# Ports.net
KiCad netlist of a schematic drawn in Altium Designer
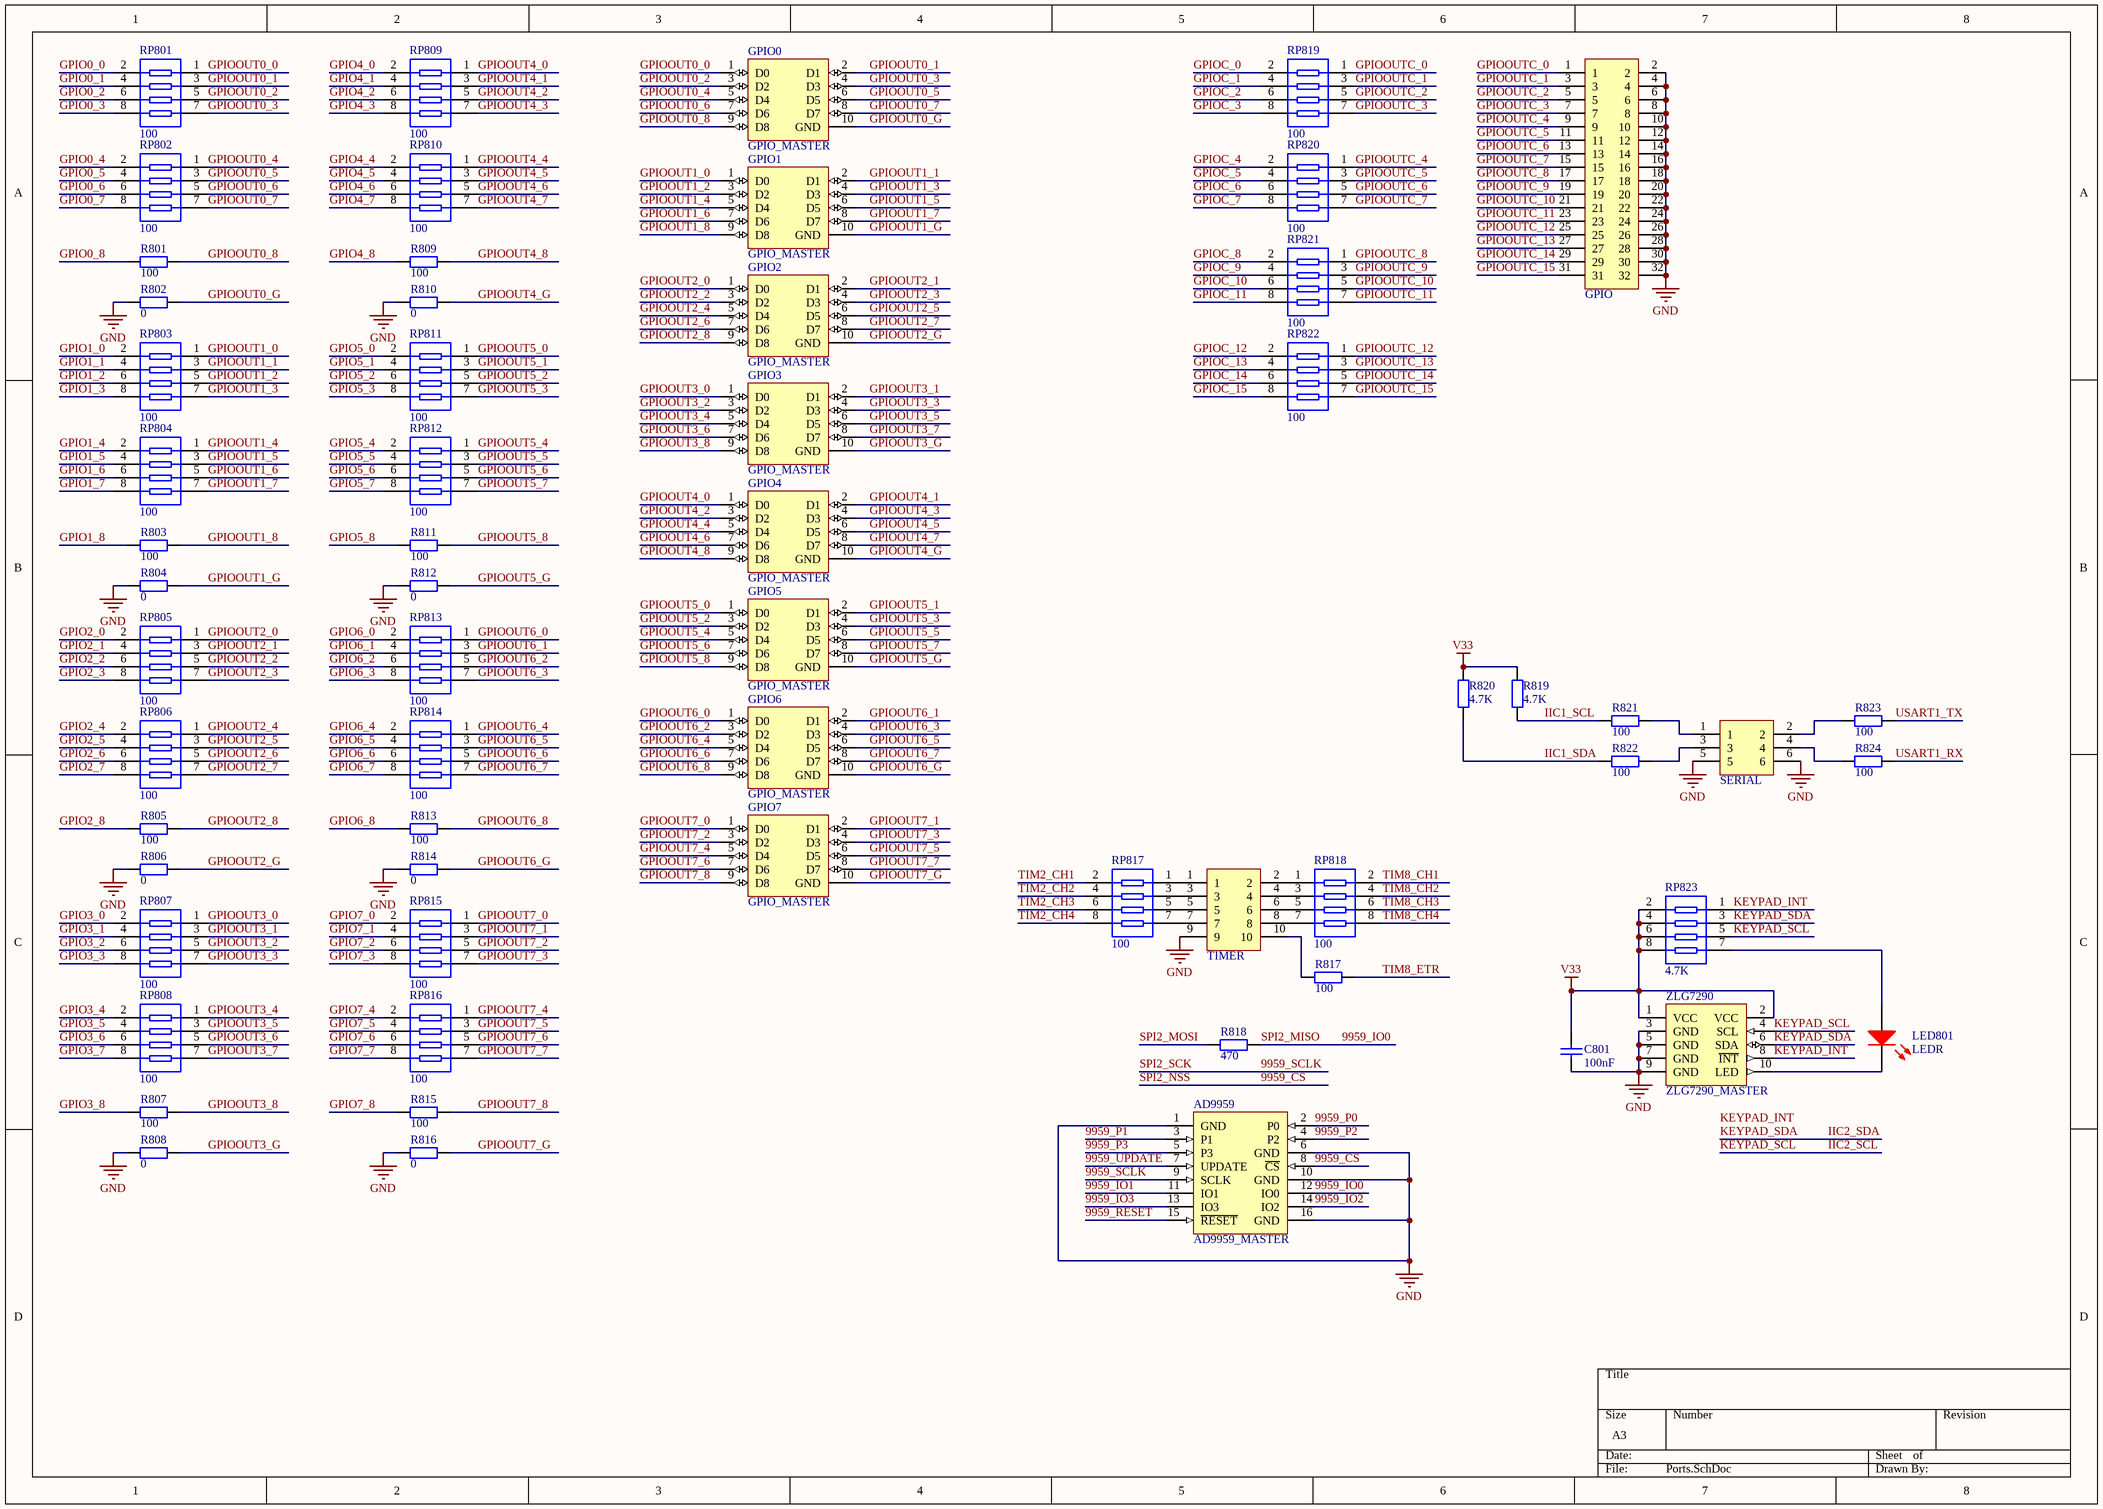
[diagram p0: Ports.SchDoc]

(export (version "E")
  (design (tool "Eeschema 10.0.6"))
  (components
    (comp (ref "AD9959")
      (value "AD9959_MASTER")
      (footprint "IDC16")
      (description "DDS module")
      (libsource (lib "Modules") (part "AD9959_MASTER"))
    )
    (comp (ref "C801")
      (value "100nF")
      (footprint "0805C")
      (description "MLCC")
      (libsource (lib "Misc") (part "MLCC"))
    )
    (comp (ref "GPIO")
      (value "Dual 16 pin port")
      (footprint "201S2X16")
      (libsource (lib "Ports2.54") (part "DPORT16"))
    )
    (comp (ref "GPIO0")
      (value "GPIO_MASTER")
      (footprint "IDC10")
      (libsource (lib "Modules") (part "GPIO_MASTER"))
    )
    (comp (ref "GPIO1")
      (value "GPIO_MASTER")
      (footprint "IDC10")
      (libsource (lib "Modules") (part "GPIO_MASTER"))
    )
    (comp (ref "GPIO2")
      (value "GPIO_MASTER")
      (footprint "IDC10")
      (libsource (lib "Modules") (part "GPIO_MASTER"))
    )
    (comp (ref "GPIO3")
      (value "GPIO_MASTER")
      (footprint "IDC10")
      (libsource (lib "Modules") (part "GPIO_MASTER"))
    )
    (comp (ref "GPIO4")
      (value "GPIO_MASTER")
      (footprint "IDC10")
      (libsource (lib "Modules") (part "GPIO_MASTER"))
    )
    (comp (ref "GPIO5")
      (value "GPIO_MASTER")
      (footprint "IDC10")
      (libsource (lib "Modules") (part "GPIO_MASTER"))
    )
    (comp (ref "GPIO6")
      (value "GPIO_MASTER")
      (footprint "IDC10")
      (libsource (lib "Modules") (part "GPIO_MASTER"))
    )
    (comp (ref "GPIO7")
      (value "GPIO_MASTER")
      (footprint "IDC10")
      (libsource (lib "Modules") (part "GPIO_MASTER"))
    )
    (comp (ref "LED801")
      (value "LEDR")
      (footprint "LED1206R")
      (description "RED LED")
      (libsource (lib "Misc") (part "LEDR"))
    )
    (comp (ref "R801")
      (value "100")
      (footprint "0603R")
      (description "Resistor")
      (libsource (lib "Misc") (part "Resistor"))
    )
    (comp (ref "R802")
      (value "0")
      (footprint "0603R")
      (description "Resistor")
      (libsource (lib "Misc") (part "Resistor"))
    )
    (comp (ref "R803")
      (value "100")
      (footprint "0603R")
      (description "Resistor")
      (libsource (lib "Misc") (part "Resistor"))
    )
    (comp (ref "R804")
      (value "0")
      (footprint "0603R")
      (description "Resistor")
      (libsource (lib "Misc") (part "Resistor"))
    )
    (comp (ref "R805")
      (value "100")
      (footprint "0603R")
      (description "Resistor")
      (libsource (lib "Misc") (part "Resistor"))
    )
    (comp (ref "R806")
      (value "0")
      (footprint "0603R")
      (description "Resistor")
      (libsource (lib "Misc") (part "Resistor"))
    )
    (comp (ref "R807")
      (value "100")
      (footprint "0603R")
      (description "Resistor")
      (libsource (lib "Misc") (part "Resistor"))
    )
    (comp (ref "R808")
      (value "0")
      (footprint "0603R")
      (description "Resistor")
      (libsource (lib "Misc") (part "Resistor"))
    )
    (comp (ref "R809")
      (value "100")
      (footprint "0603R")
      (description "Resistor")
      (libsource (lib "Misc") (part "Resistor"))
    )
    (comp (ref "R810")
      (value "0")
      (footprint "0603R")
      (description "Resistor")
      (libsource (lib "Misc") (part "Resistor"))
    )
    (comp (ref "R811")
      (value "100")
      (footprint "0603R")
      (description "Resistor")
      (libsource (lib "Misc") (part "Resistor"))
    )
    (comp (ref "R812")
      (value "0")
      (footprint "0603R")
      (description "Resistor")
      (libsource (lib "Misc") (part "Resistor"))
    )
    (comp (ref "R813")
      (value "100")
      (footprint "0603R")
      (description "Resistor")
      (libsource (lib "Misc") (part "Resistor"))
    )
    (comp (ref "R814")
      (value "0")
      (footprint "0603R")
      (description "Resistor")
      (libsource (lib "Misc") (part "Resistor"))
    )
    (comp (ref "R815")
      (value "100")
      (footprint "0603R")
      (description "Resistor")
      (libsource (lib "Misc") (part "Resistor"))
    )
    (comp (ref "R816")
      (value "0")
      (footprint "0603R")
      (description "Resistor")
      (libsource (lib "Misc") (part "Resistor"))
    )
    (comp (ref "R817")
      (value "100")
      (footprint "0603R")
      (description "Resistor")
      (libsource (lib "Misc") (part "Resistor"))
    )
    (comp (ref "R818")
      (value "470")
      (footprint "0603R")
      (description "Resistor")
      (libsource (lib "Misc") (part "Resistor"))
    )
    (comp (ref "R819")
      (value "4.7K")
      (footprint "0603R")
      (description "Resistor")
      (libsource (lib "") (part "Resistor_1"))
    )
    (comp (ref "R820")
      (value "4.7K")
      (footprint "0603R")
      (description "Resistor")
      (libsource (lib "") (part "Resistor_1"))
    )
    (comp (ref "R821")
      (value "100")
      (footprint "0603R")
      (description "Resistor")
      (libsource (lib "Misc") (part "Resistor"))
    )
    (comp (ref "R822")
      (value "100")
      (footprint "0603R")
      (description "Resistor")
      (libsource (lib "Misc") (part "Resistor"))
    )
    (comp (ref "R823")
      (value "100")
      (footprint "0603R")
      (description "Resistor")
      (libsource (lib "Misc") (part "Resistor"))
    )
    (comp (ref "R824")
      (value "100")
      (footprint "0603R")
      (description "Resistor")
      (libsource (lib "Misc") (part "Resistor"))
    )
    (comp (ref "RP801")
      (value "100")
      (footprint "8P4R_0603")
      (description "Isolated Resistor Network")
      (fields (field (name "Comment") "Res Pack"))
      (libsource (lib "Misc") (part "Res Pack"))
    )
    (comp (ref "RP802")
      (value "100")
      (footprint "8P4R_0603")
      (description "Isolated Resistor Network")
      (fields (field (name "Comment") "Res Pack"))
      (libsource (lib "Misc") (part "Res Pack"))
    )
    (comp (ref "RP803")
      (value "100")
      (footprint "8P4R_0603")
      (description "Isolated Resistor Network")
      (fields (field (name "Comment") "Res Pack"))
      (libsource (lib "Misc") (part "Res Pack"))
    )
    (comp (ref "RP804")
      (value "100")
      (footprint "8P4R_0603")
      (description "Isolated Resistor Network")
      (fields (field (name "Comment") "Res Pack"))
      (libsource (lib "Misc") (part "Res Pack"))
    )
    (comp (ref "RP805")
      (value "100")
      (footprint "8P4R_0603")
      (description "Isolated Resistor Network")
      (fields (field (name "Comment") "Res Pack"))
      (libsource (lib "Misc") (part "Res Pack"))
    )
    (comp (ref "RP806")
      (value "100")
      (footprint "8P4R_0603")
      (description "Isolated Resistor Network")
      (fields (field (name "Comment") "Res Pack"))
      (libsource (lib "Misc") (part "Res Pack"))
    )
    (comp (ref "RP807")
      (value "100")
      (footprint "8P4R_0603")
      (description "Isolated Resistor Network")
      (fields (field (name "Comment") "Res Pack"))
      (libsource (lib "Misc") (part "Res Pack"))
    )
    (comp (ref "RP808")
      (value "100")
      (footprint "8P4R_0603")
      (description "Isolated Resistor Network")
      (fields (field (name "Comment") "Res Pack"))
      (libsource (lib "Misc") (part "Res Pack"))
    )
    (comp (ref "RP809")
      (value "100")
      (footprint "8P4R_0603")
      (description "Isolated Resistor Network")
      (fields (field (name "Comment") "Res Pack"))
      (libsource (lib "Misc") (part "Res Pack"))
    )
    (comp (ref "RP810")
      (value "100")
      (footprint "8P4R_0603")
      (description "Isolated Resistor Network")
      (fields (field (name "Comment") "Res Pack"))
      (libsource (lib "Misc") (part "Res Pack"))
    )
    (comp (ref "RP811")
      (value "100")
      (footprint "8P4R_0603")
      (description "Isolated Resistor Network")
      (fields (field (name "Comment") "Res Pack"))
      (libsource (lib "Misc") (part "Res Pack"))
    )
    (comp (ref "RP812")
      (value "100")
      (footprint "8P4R_0603")
      (description "Isolated Resistor Network")
      (fields (field (name "Comment") "Res Pack"))
      (libsource (lib "Misc") (part "Res Pack"))
    )
    (comp (ref "RP813")
      (value "100")
      (footprint "8P4R_0603")
      (description "Isolated Resistor Network")
      (fields (field (name "Comment") "Res Pack"))
      (libsource (lib "Misc") (part "Res Pack"))
    )
    (comp (ref "RP814")
      (value "100")
      (footprint "8P4R_0603")
      (description "Isolated Resistor Network")
      (fields (field (name "Comment") "Res Pack"))
      (libsource (lib "Misc") (part "Res Pack"))
    )
    (comp (ref "RP815")
      (value "100")
      (footprint "8P4R_0603")
      (description "Isolated Resistor Network")
      (fields (field (name "Comment") "Res Pack"))
      (libsource (lib "Misc") (part "Res Pack"))
    )
    (comp (ref "RP816")
      (value "100")
      (footprint "8P4R_0603")
      (description "Isolated Resistor Network")
      (fields (field (name "Comment") "Res Pack"))
      (libsource (lib "Misc") (part "Res Pack"))
    )
    (comp (ref "RP817")
      (value "100")
      (footprint "8P4R_0603")
      (description "Isolated Resistor Network")
      (fields (field (name "Comment") "Res Pack"))
      (libsource (lib "Misc") (part "Res Pack"))
    )
    (comp (ref "RP818")
      (value "100")
      (footprint "8P4R_0603")
      (description "Isolated Resistor Network")
      (fields (field (name "Comment") "Res Pack"))
      (libsource (lib "Misc") (part "Res Pack"))
    )
    (comp (ref "RP819")
      (value "100")
      (footprint "8P4R_0603")
      (description "Isolated Resistor Network")
      (fields (field (name "Comment") "Res Pack"))
      (libsource (lib "Misc") (part "Res Pack"))
    )
    (comp (ref "RP820")
      (value "100")
      (footprint "8P4R_0603")
      (description "Isolated Resistor Network")
      (fields (field (name "Comment") "Res Pack"))
      (libsource (lib "Misc") (part "Res Pack"))
    )
    (comp (ref "RP821")
      (value "100")
      (footprint "8P4R_0603")
      (description "Isolated Resistor Network")
      (fields (field (name "Comment") "Res Pack"))
      (libsource (lib "Misc") (part "Res Pack"))
    )
    (comp (ref "RP822")
      (value "100")
      (footprint "8P4R_0603")
      (description "Isolated Resistor Network")
      (fields (field (name "Comment") "Res Pack"))
      (libsource (lib "Misc") (part "Res Pack"))
    )
    (comp (ref "RP823")
      (value "4.7K")
      (footprint "8P4R_0603")
      (description "Isolated Resistor Network")
      (fields (field (name "Comment") "Res Pack"))
      (libsource (lib "Misc") (part "Res Pack"))
    )
    (comp (ref "SERIAL")
      (value "Dual 3 pin port")
      (footprint "201S2X3")
      (libsource (lib "Ports2.54") (part "DPORT3"))
    )
    (comp (ref "TIMER") (value "IDC10") (footprint "IDC10") (libsource (lib "Ports2.54") (part "IDC10")))
    (comp (ref "ZLG7290")
      (value "ZLG7290_MASTER")
      (footprint "IDC10")
      (description "KEY module")
      (libsource (lib "Modules") (part "ZLG7290_MASTER"))
    )
  )
  (nets
    (net (code "1") (name "/9959_CS") (class "Default")
      (node (ref "AD9959") (pin "8") (pinfunction "~{CS}_8") (pintype "input"))
    )
    (net (code "2") (name "/9959_IO0") (class "Default")
      (node (ref "AD9959") (pin "12") (pinfunction "IO0_12") (pintype "passive"))
      (node (ref "R818") (pin "2") (pinfunction "2_2") (pintype "passive"))
    )
    (net (code "3") (name "/9959_IO1") (class "Default")
      (node (ref "AD9959") (pin "11") (pinfunction "IO1_11") (pintype "passive"))
    )
    (net (code "4") (name "/9959_IO2") (class "Default")
      (node (ref "AD9959") (pin "14") (pinfunction "IO2_14") (pintype "passive"))
    )
    (net (code "5") (name "/9959_IO3") (class "Default")
      (node (ref "AD9959") (pin "13") (pinfunction "IO3_13") (pintype "passive"))
    )
    (net (code "6") (name "/9959_P0") (class "Default")
      (node (ref "AD9959") (pin "2") (pinfunction "P0_2") (pintype "input"))
    )
    (net (code "7") (name "/9959_P1") (class "Default")
      (node (ref "AD9959") (pin "3") (pinfunction "P1_3") (pintype "input"))
    )
    (net (code "8") (name "/9959_P2") (class "Default")
      (node (ref "AD9959") (pin "4") (pinfunction "P2_4") (pintype "input"))
    )
    (net (code "9") (name "/9959_P3") (class "Default")
      (node (ref "AD9959") (pin "5") (pinfunction "P3_5") (pintype "input"))
    )
    (net (code "10") (name "/9959_RESET") (class "Default")
      (node (ref "AD9959") (pin "15") (pinfunction "~{RESET}_15") (pintype "input"))
    )
    (net (code "11") (name "/9959_SCLK") (class "Default")
      (node (ref "AD9959") (pin "9") (pinfunction "SCLK_9") (pintype "input"))
    )
    (net (code "12") (name "/9959_UPDATE") (class "Default")
      (node (ref "AD9959") (pin "7") (pinfunction "UPDATE_7") (pintype "input"))
    )
    (net (code "13") (name "/GPIO0_0") (class "Default")
      (node (ref "RP801") (pin "2") (pinfunction "2_2") (pintype "passive"))
    )
    (net (code "14") (name "/GPIO0_1") (class "Default")
      (node (ref "RP801") (pin "4") (pinfunction "4_4") (pintype "passive"))
    )
    (net (code "15") (name "/GPIO0_2") (class "Default")
      (node (ref "RP801") (pin "6") (pinfunction "6_6") (pintype "passive"))
    )
    (net (code "16") (name "/GPIO0_3") (class "Default")
      (node (ref "RP801") (pin "8") (pinfunction "8_8") (pintype "passive"))
    )
    (net (code "17") (name "/GPIO0_4") (class "Default")
      (node (ref "RP802") (pin "2") (pinfunction "2_2") (pintype "passive"))
    )
    (net (code "18") (name "/GPIO0_5") (class "Default")
      (node (ref "RP802") (pin "4") (pinfunction "4_4") (pintype "passive"))
    )
    (net (code "19") (name "/GPIO0_6") (class "Default")
      (node (ref "RP802") (pin "6") (pinfunction "6_6") (pintype "passive"))
    )
    (net (code "20") (name "/GPIO0_7") (class "Default")
      (node (ref "RP802") (pin "8") (pinfunction "8_8") (pintype "passive"))
    )
    (net (code "21") (name "/GPIO0_8") (class "Default")
      (node (ref "R801") (pin "1") (pinfunction "1_1") (pintype "passive"))
    )
    (net (code "22") (name "/GPIO1_0") (class "Default")
      (node (ref "RP803") (pin "2") (pinfunction "2_2") (pintype "passive"))
    )
    (net (code "23") (name "/GPIO1_1") (class "Default")
      (node (ref "RP803") (pin "4") (pinfunction "4_4") (pintype "passive"))
    )
    (net (code "24") (name "/GPIO1_2") (class "Default")
      (node (ref "RP803") (pin "6") (pinfunction "6_6") (pintype "passive"))
    )
    (net (code "25") (name "/GPIO1_3") (class "Default")
      (node (ref "RP803") (pin "8") (pinfunction "8_8") (pintype "passive"))
    )
    (net (code "26") (name "/GPIO1_4") (class "Default")
      (node (ref "RP804") (pin "2") (pinfunction "2_2") (pintype "passive"))
    )
    (net (code "27") (name "/GPIO1_5") (class "Default")
      (node (ref "RP804") (pin "4") (pinfunction "4_4") (pintype "passive"))
    )
    (net (code "28") (name "/GPIO1_6") (class "Default")
      (node (ref "RP804") (pin "6") (pinfunction "6_6") (pintype "passive"))
    )
    (net (code "29") (name "/GPIO1_7") (class "Default")
      (node (ref "RP804") (pin "8") (pinfunction "8_8") (pintype "passive"))
    )
    (net (code "30") (name "/GPIO1_8") (class "Default")
      (node (ref "R803") (pin "1") (pinfunction "1_1") (pintype "passive"))
    )
    (net (code "31") (name "/GPIO2_0") (class "Default")
      (node (ref "RP805") (pin "2") (pinfunction "2_2") (pintype "passive"))
    )
    (net (code "32") (name "/GPIO2_1") (class "Default")
      (node (ref "RP805") (pin "4") (pinfunction "4_4") (pintype "passive"))
    )
    (net (code "33") (name "/GPIO2_2") (class "Default")
      (node (ref "RP805") (pin "6") (pinfunction "6_6") (pintype "passive"))
    )
    (net (code "34") (name "/GPIO2_3") (class "Default")
      (node (ref "RP805") (pin "8") (pinfunction "8_8") (pintype "passive"))
    )
    (net (code "35") (name "/GPIO2_4") (class "Default")
      (node (ref "RP806") (pin "2") (pinfunction "2_2") (pintype "passive"))
    )
    (net (code "36") (name "/GPIO2_5") (class "Default")
      (node (ref "RP806") (pin "4") (pinfunction "4_4") (pintype "passive"))
    )
    (net (code "37") (name "/GPIO2_6") (class "Default")
      (node (ref "RP806") (pin "6") (pinfunction "6_6") (pintype "passive"))
    )
    (net (code "38") (name "/GPIO2_7") (class "Default")
      (node (ref "RP806") (pin "8") (pinfunction "8_8") (pintype "passive"))
    )
    (net (code "39") (name "/GPIO2_8") (class "Default")
      (node (ref "R805") (pin "1") (pinfunction "1_1") (pintype "passive"))
    )
    (net (code "40") (name "/GPIO3_0") (class "Default")
      (node (ref "RP807") (pin "2") (pinfunction "2_2") (pintype "passive"))
    )
    (net (code "41") (name "/GPIO3_1") (class "Default")
      (node (ref "RP807") (pin "4") (pinfunction "4_4") (pintype "passive"))
    )
    (net (code "42") (name "/GPIO3_2") (class "Default")
      (node (ref "RP807") (pin "6") (pinfunction "6_6") (pintype "passive"))
    )
    (net (code "43") (name "/GPIO3_3") (class "Default")
      (node (ref "RP807") (pin "8") (pinfunction "8_8") (pintype "passive"))
    )
    (net (code "44") (name "/GPIO3_4") (class "Default")
      (node (ref "RP808") (pin "2") (pinfunction "2_2") (pintype "passive"))
    )
    (net (code "45") (name "/GPIO3_5") (class "Default")
      (node (ref "RP808") (pin "4") (pinfunction "4_4") (pintype "passive"))
    )
    (net (code "46") (name "/GPIO3_6") (class "Default")
      (node (ref "RP808") (pin "6") (pinfunction "6_6") (pintype "passive"))
    )
    (net (code "47") (name "/GPIO3_7") (class "Default")
      (node (ref "RP808") (pin "8") (pinfunction "8_8") (pintype "passive"))
    )
    (net (code "48") (name "/GPIO3_8") (class "Default")
      (node (ref "R807") (pin "1") (pinfunction "1_1") (pintype "passive"))
    )
    (net (code "49") (name "/GPIO4_0") (class "Default")
      (node (ref "RP809") (pin "2") (pinfunction "2_2") (pintype "passive"))
    )
    (net (code "50") (name "/GPIO4_1") (class "Default")
      (node (ref "RP809") (pin "4") (pinfunction "4_4") (pintype "passive"))
    )
    (net (code "51") (name "/GPIO4_2") (class "Default")
      (node (ref "RP809") (pin "6") (pinfunction "6_6") (pintype "passive"))
    )
    (net (code "52") (name "/GPIO4_3") (class "Default")
      (node (ref "RP809") (pin "8") (pinfunction "8_8") (pintype "passive"))
    )
    (net (code "53") (name "/GPIO4_4") (class "Default")
      (node (ref "RP810") (pin "2") (pinfunction "2_2") (pintype "passive"))
    )
    (net (code "54") (name "/GPIO4_5") (class "Default")
      (node (ref "RP810") (pin "4") (pinfunction "4_4") (pintype "passive"))
    )
    (net (code "55") (name "/GPIO4_6") (class "Default")
      (node (ref "RP810") (pin "6") (pinfunction "6_6") (pintype "passive"))
    )
    (net (code "56") (name "/GPIO4_7") (class "Default")
      (node (ref "RP810") (pin "8") (pinfunction "8_8") (pintype "passive"))
    )
    (net (code "57") (name "/GPIO4_8") (class "Default")
      (node (ref "R809") (pin "1") (pinfunction "1_1") (pintype "passive"))
    )
    (net (code "58") (name "/GPIO5_0") (class "Default")
      (node (ref "RP811") (pin "2") (pinfunction "2_2") (pintype "passive"))
    )
    (net (code "59") (name "/GPIO5_1") (class "Default")
      (node (ref "RP811") (pin "4") (pinfunction "4_4") (pintype "passive"))
    )
    (net (code "60") (name "/GPIO5_2") (class "Default")
      (node (ref "RP811") (pin "6") (pinfunction "6_6") (pintype "passive"))
    )
    (net (code "61") (name "/GPIO5_3") (class "Default")
      (node (ref "RP811") (pin "8") (pinfunction "8_8") (pintype "passive"))
    )
    (net (code "62") (name "/GPIO5_4") (class "Default")
      (node (ref "RP812") (pin "2") (pinfunction "2_2") (pintype "passive"))
    )
    (net (code "63") (name "/GPIO5_5") (class "Default")
      (node (ref "RP812") (pin "4") (pinfunction "4_4") (pintype "passive"))
    )
    (net (code "64") (name "/GPIO5_6") (class "Default")
      (node (ref "RP812") (pin "6") (pinfunction "6_6") (pintype "passive"))
    )
    (net (code "65") (name "/GPIO5_7") (class "Default")
      (node (ref "RP812") (pin "8") (pinfunction "8_8") (pintype "passive"))
    )
    (net (code "66") (name "/GPIO5_8") (class "Default")
      (node (ref "R811") (pin "1") (pinfunction "1_1") (pintype "passive"))
    )
    (net (code "67") (name "/GPIO6_0") (class "Default")
      (node (ref "RP813") (pin "2") (pinfunction "2_2") (pintype "passive"))
    )
    (net (code "68") (name "/GPIO6_1") (class "Default")
      (node (ref "RP813") (pin "4") (pinfunction "4_4") (pintype "passive"))
    )
    (net (code "69") (name "/GPIO6_2") (class "Default")
      (node (ref "RP813") (pin "6") (pinfunction "6_6") (pintype "passive"))
    )
    (net (code "70") (name "/GPIO6_3") (class "Default")
      (node (ref "RP813") (pin "8") (pinfunction "8_8") (pintype "passive"))
    )
    (net (code "71") (name "/GPIO6_4") (class "Default")
      (node (ref "RP814") (pin "2") (pinfunction "2_2") (pintype "passive"))
    )
    (net (code "72") (name "/GPIO6_5") (class "Default")
      (node (ref "RP814") (pin "4") (pinfunction "4_4") (pintype "passive"))
    )
    (net (code "73") (name "/GPIO6_6") (class "Default")
      (node (ref "RP814") (pin "6") (pinfunction "6_6") (pintype "passive"))
    )
    (net (code "74") (name "/GPIO6_7") (class "Default")
      (node (ref "RP814") (pin "8") (pinfunction "8_8") (pintype "passive"))
    )
    (net (code "75") (name "/GPIO6_8") (class "Default")
      (node (ref "R813") (pin "1") (pinfunction "1_1") (pintype "passive"))
    )
    (net (code "76") (name "/GPIO7_0") (class "Default")
      (node (ref "RP815") (pin "2") (pinfunction "2_2") (pintype "passive"))
    )
    (net (code "77") (name "/GPIO7_1") (class "Default")
      (node (ref "RP815") (pin "4") (pinfunction "4_4") (pintype "passive"))
    )
    (net (code "78") (name "/GPIO7_2") (class "Default")
      (node (ref "RP815") (pin "6") (pinfunction "6_6") (pintype "passive"))
    )
    (net (code "79") (name "/GPIO7_3") (class "Default")
      (node (ref "RP815") (pin "8") (pinfunction "8_8") (pintype "passive"))
    )
    (net (code "80") (name "/GPIO7_4") (class "Default")
      (node (ref "RP816") (pin "2") (pinfunction "2_2") (pintype "passive"))
    )
    (net (code "81") (name "/GPIO7_5") (class "Default")
      (node (ref "RP816") (pin "4") (pinfunction "4_4") (pintype "passive"))
    )
    (net (code "82") (name "/GPIO7_6") (class "Default")
      (node (ref "RP816") (pin "6") (pinfunction "6_6") (pintype "passive"))
    )
    (net (code "83") (name "/GPIO7_7") (class "Default")
      (node (ref "RP816") (pin "8") (pinfunction "8_8") (pintype "passive"))
    )
    (net (code "84") (name "/GPIO7_8") (class "Default")
      (node (ref "R815") (pin "1") (pinfunction "1_1") (pintype "passive"))
    )
    (net (code "85") (name "/GPIOC_0") (class "Default")
      (node (ref "RP819") (pin "2") (pinfunction "2_2") (pintype "passive"))
    )
    (net (code "86") (name "/GPIOC_1") (class "Default")
      (node (ref "RP819") (pin "4") (pinfunction "4_4") (pintype "passive"))
    )
    (net (code "87") (name "/GPIOC_2") (class "Default")
      (node (ref "RP819") (pin "6") (pinfunction "6_6") (pintype "passive"))
    )
    (net (code "88") (name "/GPIOC_3") (class "Default")
      (node (ref "RP819") (pin "8") (pinfunction "8_8") (pintype "passive"))
    )
    (net (code "89") (name "/GPIOC_4") (class "Default")
      (node (ref "RP820") (pin "2") (pinfunction "2_2") (pintype "passive"))
    )
    (net (code "90") (name "/GPIOC_5") (class "Default")
      (node (ref "RP820") (pin "4") (pinfunction "4_4") (pintype "passive"))
    )
    (net (code "91") (name "/GPIOC_6") (class "Default")
      (node (ref "RP820") (pin "6") (pinfunction "6_6") (pintype "passive"))
    )
    (net (code "92") (name "/GPIOC_7") (class "Default")
      (node (ref "RP820") (pin "8") (pinfunction "8_8") (pintype "passive"))
    )
    (net (code "93") (name "/GPIOC_8") (class "Default")
      (node (ref "RP821") (pin "2") (pinfunction "2_2") (pintype "passive"))
    )
    (net (code "94") (name "/GPIOC_9") (class "Default")
      (node (ref "RP821") (pin "4") (pinfunction "4_4") (pintype "passive"))
    )
    (net (code "95") (name "/GPIOC_10") (class "Default")
      (node (ref "RP821") (pin "6") (pinfunction "6_6") (pintype "passive"))
    )
    (net (code "96") (name "/GPIOC_11") (class "Default")
      (node (ref "RP821") (pin "8") (pinfunction "8_8") (pintype "passive"))
    )
    (net (code "97") (name "/GPIOC_12") (class "Default")
      (node (ref "RP822") (pin "2") (pinfunction "2_2") (pintype "passive"))
    )
    (net (code "98") (name "/GPIOC_13") (class "Default")
      (node (ref "RP822") (pin "4") (pinfunction "4_4") (pintype "passive"))
    )
    (net (code "99") (name "/GPIOC_14") (class "Default")
      (node (ref "RP822") (pin "6") (pinfunction "6_6") (pintype "passive"))
    )
    (net (code "100") (name "/GPIOC_15") (class "Default")
      (node (ref "RP822") (pin "8") (pinfunction "8_8") (pintype "passive"))
    )
    (net (code "101") (name "/GPIOOUT0_0") (class "Default")
      (node (ref "GPIO0") (pin "1") (pinfunction "D0_1") (pintype "bidirectional"))
      (node (ref "RP801") (pin "1") (pinfunction "1_1") (pintype "passive"))
    )
    (net (code "102") (name "/GPIOOUT0_1") (class "Default")
      (node (ref "GPIO0") (pin "2") (pinfunction "D1_2") (pintype "bidirectional"))
      (node (ref "RP801") (pin "3") (pinfunction "3_3") (pintype "passive"))
    )
    (net (code "103") (name "/GPIOOUT0_2") (class "Default")
      (node (ref "GPIO0") (pin "3") (pinfunction "D2_3") (pintype "bidirectional"))
      (node (ref "RP801") (pin "5") (pinfunction "5_5") (pintype "passive"))
    )
    (net (code "104") (name "/GPIOOUT0_3") (class "Default")
      (node (ref "GPIO0") (pin "4") (pinfunction "D3_4") (pintype "bidirectional"))
      (node (ref "RP801") (pin "7") (pinfunction "7_7") (pintype "passive"))
    )
    (net (code "105") (name "/GPIOOUT0_4") (class "Default")
      (node (ref "GPIO0") (pin "5") (pinfunction "D4_5") (pintype "bidirectional"))
      (node (ref "RP802") (pin "1") (pinfunction "1_1") (pintype "passive"))
    )
    (net (code "106") (name "/GPIOOUT0_5") (class "Default")
      (node (ref "GPIO0") (pin "6") (pinfunction "D5_6") (pintype "bidirectional"))
      (node (ref "RP802") (pin "3") (pinfunction "3_3") (pintype "passive"))
    )
    (net (code "107") (name "/GPIOOUT0_6") (class "Default")
      (node (ref "GPIO0") (pin "7") (pinfunction "D6_7") (pintype "bidirectional"))
      (node (ref "RP802") (pin "5") (pinfunction "5_5") (pintype "passive"))
    )
    (net (code "108") (name "/GPIOOUT0_7") (class "Default")
      (node (ref "GPIO0") (pin "8") (pinfunction "D7_8") (pintype "bidirectional"))
      (node (ref "RP802") (pin "7") (pinfunction "7_7") (pintype "passive"))
    )
    (net (code "109") (name "/GPIOOUT0_8") (class "Default")
      (node (ref "GPIO0") (pin "9") (pinfunction "D8_9") (pintype "bidirectional"))
      (node (ref "R801") (pin "2") (pinfunction "2_2") (pintype "passive"))
    )
    (net (code "110") (name "/GPIOOUT0_G") (class "Default")
      (node (ref "GPIO0") (pin "10") (pinfunction "GND_10") (pintype "power_in"))
      (node (ref "R802") (pin "2") (pinfunction "2_2") (pintype "passive"))
    )
    (net (code "111") (name "/GPIOOUT1_0") (class "Default")
      (node (ref "GPIO1") (pin "1") (pinfunction "D0_1") (pintype "bidirectional"))
      (node (ref "RP803") (pin "1") (pinfunction "1_1") (pintype "passive"))
    )
    (net (code "112") (name "/GPIOOUT1_1") (class "Default")
      (node (ref "GPIO1") (pin "2") (pinfunction "D1_2") (pintype "bidirectional"))
      (node (ref "RP803") (pin "3") (pinfunction "3_3") (pintype "passive"))
    )
    (net (code "113") (name "/GPIOOUT1_2") (class "Default")
      (node (ref "GPIO1") (pin "3") (pinfunction "D2_3") (pintype "bidirectional"))
      (node (ref "RP803") (pin "5") (pinfunction "5_5") (pintype "passive"))
    )
    (net (code "114") (name "/GPIOOUT1_3") (class "Default")
      (node (ref "GPIO1") (pin "4") (pinfunction "D3_4") (pintype "bidirectional"))
      (node (ref "RP803") (pin "7") (pinfunction "7_7") (pintype "passive"))
    )
    (net (code "115") (name "/GPIOOUT1_4") (class "Default")
      (node (ref "GPIO1") (pin "5") (pinfunction "D4_5") (pintype "bidirectional"))
      (node (ref "RP804") (pin "1") (pinfunction "1_1") (pintype "passive"))
    )
    (net (code "116") (name "/GPIOOUT1_5") (class "Default")
      (node (ref "GPIO1") (pin "6") (pinfunction "D5_6") (pintype "bidirectional"))
      (node (ref "RP804") (pin "3") (pinfunction "3_3") (pintype "passive"))
    )
    (net (code "117") (name "/GPIOOUT1_6") (class "Default")
      (node (ref "GPIO1") (pin "7") (pinfunction "D6_7") (pintype "bidirectional"))
      (node (ref "RP804") (pin "5") (pinfunction "5_5") (pintype "passive"))
    )
    (net (code "118") (name "/GPIOOUT1_7") (class "Default")
      (node (ref "GPIO1") (pin "8") (pinfunction "D7_8") (pintype "bidirectional"))
      (node (ref "RP804") (pin "7") (pinfunction "7_7") (pintype "passive"))
    )
    (net (code "119") (name "/GPIOOUT1_8") (class "Default")
      (node (ref "GPIO1") (pin "9") (pinfunction "D8_9") (pintype "bidirectional"))
      (node (ref "R803") (pin "2") (pinfunction "2_2") (pintype "passive"))
    )
    (net (code "120") (name "/GPIOOUT1_G") (class "Default")
      (node (ref "GPIO1") (pin "10") (pinfunction "GND_10") (pintype "power_in"))
      (node (ref "R804") (pin "2") (pinfunction "2_2") (pintype "passive"))
    )
    (net (code "121") (name "/GPIOOUT2_0") (class "Default")
      (node (ref "GPIO2") (pin "1") (pinfunction "D0_1") (pintype "bidirectional"))
      (node (ref "RP805") (pin "1") (pinfunction "1_1") (pintype "passive"))
    )
    (net (code "122") (name "/GPIOOUT2_1") (class "Default")
      (node (ref "GPIO2") (pin "2") (pinfunction "D1_2") (pintype "bidirectional"))
      (node (ref "RP805") (pin "3") (pinfunction "3_3") (pintype "passive"))
    )
    (net (code "123") (name "/GPIOOUT2_2") (class "Default")
      (node (ref "GPIO2") (pin "3") (pinfunction "D2_3") (pintype "bidirectional"))
      (node (ref "RP805") (pin "5") (pinfunction "5_5") (pintype "passive"))
    )
    (net (code "124") (name "/GPIOOUT2_3") (class "Default")
      (node (ref "GPIO2") (pin "4") (pinfunction "D3_4") (pintype "bidirectional"))
      (node (ref "RP805") (pin "7") (pinfunction "7_7") (pintype "passive"))
    )
    (net (code "125") (name "/GPIOOUT2_4") (class "Default")
      (node (ref "GPIO2") (pin "5") (pinfunction "D4_5") (pintype "bidirectional"))
      (node (ref "RP806") (pin "1") (pinfunction "1_1") (pintype "passive"))
    )
    (net (code "126") (name "/GPIOOUT2_5") (class "Default")
      (node (ref "GPIO2") (pin "6") (pinfunction "D5_6") (pintype "bidirectional"))
      (node (ref "RP806") (pin "3") (pinfunction "3_3") (pintype "passive"))
    )
    (net (code "127") (name "/GPIOOUT2_6") (class "Default")
      (node (ref "GPIO2") (pin "7") (pinfunction "D6_7") (pintype "bidirectional"))
      (node (ref "RP806") (pin "5") (pinfunction "5_5") (pintype "passive"))
    )
    (net (code "128") (name "/GPIOOUT2_7") (class "Default")
      (node (ref "GPIO2") (pin "8") (pinfunction "D7_8") (pintype "bidirectional"))
      (node (ref "RP806") (pin "7") (pinfunction "7_7") (pintype "passive"))
    )
    (net (code "129") (name "/GPIOOUT2_8") (class "Default")
      (node (ref "GPIO2") (pin "9") (pinfunction "D8_9") (pintype "bidirectional"))
      (node (ref "R805") (pin "2") (pinfunction "2_2") (pintype "passive"))
    )
    (net (code "130") (name "/GPIOOUT2_G") (class "Default")
      (node (ref "GPIO2") (pin "10") (pinfunction "GND_10") (pintype "power_in"))
      (node (ref "R806") (pin "2") (pinfunction "2_2") (pintype "passive"))
    )
    (net (code "131") (name "/GPIOOUT3_0") (class "Default")
      (node (ref "GPIO3") (pin "1") (pinfunction "D0_1") (pintype "bidirectional"))
      (node (ref "RP807") (pin "1") (pinfunction "1_1") (pintype "passive"))
    )
    (net (code "132") (name "/GPIOOUT3_1") (class "Default")
      (node (ref "GPIO3") (pin "2") (pinfunction "D1_2") (pintype "bidirectional"))
      (node (ref "RP807") (pin "3") (pinfunction "3_3") (pintype "passive"))
    )
    (net (code "133") (name "/GPIOOUT3_2") (class "Default")
      (node (ref "GPIO3") (pin "3") (pinfunction "D2_3") (pintype "bidirectional"))
      (node (ref "RP807") (pin "5") (pinfunction "5_5") (pintype "passive"))
    )
    (net (code "134") (name "/GPIOOUT3_3") (class "Default")
      (node (ref "GPIO3") (pin "4") (pinfunction "D3_4") (pintype "bidirectional"))
      (node (ref "RP807") (pin "7") (pinfunction "7_7") (pintype "passive"))
    )
    (net (code "135") (name "/GPIOOUT3_4") (class "Default")
      (node (ref "GPIO3") (pin "5") (pinfunction "D4_5") (pintype "bidirectional"))
      (node (ref "RP808") (pin "1") (pinfunction "1_1") (pintype "passive"))
    )
    (net (code "136") (name "/GPIOOUT3_5") (class "Default")
      (node (ref "GPIO3") (pin "6") (pinfunction "D5_6") (pintype "bidirectional"))
      (node (ref "RP808") (pin "3") (pinfunction "3_3") (pintype "passive"))
    )
    (net (code "137") (name "/GPIOOUT3_6") (class "Default")
      (node (ref "GPIO3") (pin "7") (pinfunction "D6_7") (pintype "bidirectional"))
      (node (ref "RP808") (pin "5") (pinfunction "5_5") (pintype "passive"))
    )
    (net (code "138") (name "/GPIOOUT3_7") (class "Default")
      (node (ref "GPIO3") (pin "8") (pinfunction "D7_8") (pintype "bidirectional"))
      (node (ref "RP808") (pin "7") (pinfunction "7_7") (pintype "passive"))
    )
    (net (code "139") (name "/GPIOOUT3_8") (class "Default")
      (node (ref "GPIO3") (pin "9") (pinfunction "D8_9") (pintype "bidirectional"))
      (node (ref "R807") (pin "2") (pinfunction "2_2") (pintype "passive"))
    )
    (net (code "140") (name "/GPIOOUT3_G") (class "Default")
      (node (ref "GPIO3") (pin "10") (pinfunction "GND_10") (pintype "power_in"))
      (node (ref "R808") (pin "2") (pinfunction "2_2") (pintype "passive"))
    )
    (net (code "141") (name "/GPIOOUT4_0") (class "Default")
      (node (ref "GPIO4") (pin "1") (pinfunction "D0_1") (pintype "bidirectional"))
      (node (ref "RP809") (pin "1") (pinfunction "1_1") (pintype "passive"))
    )
    (net (code "142") (name "/GPIOOUT4_1") (class "Default")
      (node (ref "GPIO4") (pin "2") (pinfunction "D1_2") (pintype "bidirectional"))
      (node (ref "RP809") (pin "3") (pinfunction "3_3") (pintype "passive"))
    )
    (net (code "143") (name "/GPIOOUT4_2") (class "Default")
      (node (ref "GPIO4") (pin "3") (pinfunction "D2_3") (pintype "bidirectional"))
      (node (ref "RP809") (pin "5") (pinfunction "5_5") (pintype "passive"))
    )
    (net (code "144") (name "/GPIOOUT4_3") (class "Default")
      (node (ref "GPIO4") (pin "4") (pinfunction "D3_4") (pintype "bidirectional"))
      (node (ref "RP809") (pin "7") (pinfunction "7_7") (pintype "passive"))
    )
    (net (code "145") (name "/GPIOOUT4_4") (class "Default")
      (node (ref "GPIO4") (pin "5") (pinfunction "D4_5") (pintype "bidirectional"))
      (node (ref "RP810") (pin "1") (pinfunction "1_1") (pintype "passive"))
    )
    (net (code "146") (name "/GPIOOUT4_5") (class "Default")
      (node (ref "GPIO4") (pin "6") (pinfunction "D5_6") (pintype "bidirectional"))
      (node (ref "RP810") (pin "3") (pinfunction "3_3") (pintype "passive"))
    )
    (net (code "147") (name "/GPIOOUT4_6") (class "Default")
      (node (ref "GPIO4") (pin "7") (pinfunction "D6_7") (pintype "bidirectional"))
      (node (ref "RP810") (pin "5") (pinfunction "5_5") (pintype "passive"))
    )
    (net (code "148") (name "/GPIOOUT4_7") (class "Default")
      (node (ref "GPIO4") (pin "8") (pinfunction "D7_8") (pintype "bidirectional"))
      (node (ref "RP810") (pin "7") (pinfunction "7_7") (pintype "passive"))
    )
    (net (code "149") (name "/GPIOOUT4_8") (class "Default")
      (node (ref "GPIO4") (pin "9") (pinfunction "D8_9") (pintype "bidirectional"))
      (node (ref "R809") (pin "2") (pinfunction "2_2") (pintype "passive"))
    )
    (net (code "150") (name "/GPIOOUT4_G") (class "Default")
      (node (ref "GPIO4") (pin "10") (pinfunction "GND_10") (pintype "power_in"))
      (node (ref "R810") (pin "2") (pinfunction "2_2") (pintype "passive"))
    )
    (net (code "151") (name "/GPIOOUT5_0") (class "Default")
      (node (ref "GPIO5") (pin "1") (pinfunction "D0_1") (pintype "bidirectional"))
      (node (ref "RP811") (pin "1") (pinfunction "1_1") (pintype "passive"))
    )
    (net (code "152") (name "/GPIOOUT5_1") (class "Default")
      (node (ref "GPIO5") (pin "2") (pinfunction "D1_2") (pintype "bidirectional"))
      (node (ref "RP811") (pin "3") (pinfunction "3_3") (pintype "passive"))
    )
    (net (code "153") (name "/GPIOOUT5_2") (class "Default")
      (node (ref "GPIO5") (pin "3") (pinfunction "D2_3") (pintype "bidirectional"))
      (node (ref "RP811") (pin "5") (pinfunction "5_5") (pintype "passive"))
    )
    (net (code "154") (name "/GPIOOUT5_3") (class "Default")
      (node (ref "GPIO5") (pin "4") (pinfunction "D3_4") (pintype "bidirectional"))
      (node (ref "RP811") (pin "7") (pinfunction "7_7") (pintype "passive"))
    )
    (net (code "155") (name "/GPIOOUT5_4") (class "Default")
      (node (ref "GPIO5") (pin "5") (pinfunction "D4_5") (pintype "bidirectional"))
      (node (ref "RP812") (pin "1") (pinfunction "1_1") (pintype "passive"))
    )
    (net (code "156") (name "/GPIOOUT5_5") (class "Default")
      (node (ref "GPIO5") (pin "6") (pinfunction "D5_6") (pintype "bidirectional"))
      (node (ref "RP812") (pin "3") (pinfunction "3_3") (pintype "passive"))
    )
    (net (code "157") (name "/GPIOOUT5_6") (class "Default")
      (node (ref "GPIO5") (pin "7") (pinfunction "D6_7") (pintype "bidirectional"))
      (node (ref "RP812") (pin "5") (pinfunction "5_5") (pintype "passive"))
    )
    (net (code "158") (name "/GPIOOUT5_7") (class "Default")
      (node (ref "GPIO5") (pin "8") (pinfunction "D7_8") (pintype "bidirectional"))
      (node (ref "RP812") (pin "7") (pinfunction "7_7") (pintype "passive"))
    )
    (net (code "159") (name "/GPIOOUT5_8") (class "Default")
      (node (ref "GPIO5") (pin "9") (pinfunction "D8_9") (pintype "bidirectional"))
      (node (ref "R811") (pin "2") (pinfunction "2_2") (pintype "passive"))
    )
    (net (code "160") (name "/GPIOOUT5_G") (class "Default")
      (node (ref "GPIO5") (pin "10") (pinfunction "GND_10") (pintype "power_in"))
      (node (ref "R812") (pin "2") (pinfunction "2_2") (pintype "passive"))
    )
    (net (code "161") (name "/GPIOOUT6_0") (class "Default")
      (node (ref "GPIO6") (pin "1") (pinfunction "D0_1") (pintype "bidirectional"))
      (node (ref "RP813") (pin "1") (pinfunction "1_1") (pintype "passive"))
    )
    (net (code "162") (name "/GPIOOUT6_1") (class "Default")
      (node (ref "GPIO6") (pin "2") (pinfunction "D1_2") (pintype "bidirectional"))
      (node (ref "RP813") (pin "3") (pinfunction "3_3") (pintype "passive"))
    )
    (net (code "163") (name "/GPIOOUT6_2") (class "Default")
      (node (ref "GPIO6") (pin "3") (pinfunction "D2_3") (pintype "bidirectional"))
      (node (ref "RP813") (pin "5") (pinfunction "5_5") (pintype "passive"))
    )
    (net (code "164") (name "/GPIOOUT6_3") (class "Default")
      (node (ref "GPIO6") (pin "4") (pinfunction "D3_4") (pintype "bidirectional"))
      (node (ref "RP813") (pin "7") (pinfunction "7_7") (pintype "passive"))
    )
    (net (code "165") (name "/GPIOOUT6_4") (class "Default")
      (node (ref "GPIO6") (pin "5") (pinfunction "D4_5") (pintype "bidirectional"))
      (node (ref "RP814") (pin "1") (pinfunction "1_1") (pintype "passive"))
    )
    (net (code "166") (name "/GPIOOUT6_5") (class "Default")
      (node (ref "GPIO6") (pin "6") (pinfunction "D5_6") (pintype "bidirectional"))
      (node (ref "RP814") (pin "3") (pinfunction "3_3") (pintype "passive"))
    )
    (net (code "167") (name "/GPIOOUT6_6") (class "Default")
      (node (ref "GPIO6") (pin "7") (pinfunction "D6_7") (pintype "bidirectional"))
      (node (ref "RP814") (pin "5") (pinfunction "5_5") (pintype "passive"))
    )
    (net (code "168") (name "/GPIOOUT6_7") (class "Default")
      (node (ref "GPIO6") (pin "8") (pinfunction "D7_8") (pintype "bidirectional"))
      (node (ref "RP814") (pin "7") (pinfunction "7_7") (pintype "passive"))
    )
    (net (code "169") (name "/GPIOOUT6_8") (class "Default")
      (node (ref "GPIO6") (pin "9") (pinfunction "D8_9") (pintype "bidirectional"))
      (node (ref "R813") (pin "2") (pinfunction "2_2") (pintype "passive"))
    )
    (net (code "170") (name "/GPIOOUT6_G") (class "Default")
      (node (ref "GPIO6") (pin "10") (pinfunction "GND_10") (pintype "power_in"))
      (node (ref "R814") (pin "2") (pinfunction "2_2") (pintype "passive"))
    )
    (net (code "171") (name "/GPIOOUT7_0") (class "Default")
      (node (ref "GPIO7") (pin "1") (pinfunction "D0_1") (pintype "bidirectional"))
      (node (ref "RP815") (pin "1") (pinfunction "1_1") (pintype "passive"))
    )
    (net (code "172") (name "/GPIOOUT7_1") (class "Default")
      (node (ref "GPIO7") (pin "2") (pinfunction "D1_2") (pintype "bidirectional"))
      (node (ref "RP815") (pin "3") (pinfunction "3_3") (pintype "passive"))
    )
    (net (code "173") (name "/GPIOOUT7_2") (class "Default")
      (node (ref "GPIO7") (pin "3") (pinfunction "D2_3") (pintype "bidirectional"))
      (node (ref "RP815") (pin "5") (pinfunction "5_5") (pintype "passive"))
    )
    (net (code "174") (name "/GPIOOUT7_3") (class "Default")
      (node (ref "GPIO7") (pin "4") (pinfunction "D3_4") (pintype "bidirectional"))
      (node (ref "RP815") (pin "7") (pinfunction "7_7") (pintype "passive"))
    )
    (net (code "175") (name "/GPIOOUT7_4") (class "Default")
      (node (ref "GPIO7") (pin "5") (pinfunction "D4_5") (pintype "bidirectional"))
      (node (ref "RP816") (pin "1") (pinfunction "1_1") (pintype "passive"))
    )
    (net (code "176") (name "/GPIOOUT7_5") (class "Default")
      (node (ref "GPIO7") (pin "6") (pinfunction "D5_6") (pintype "bidirectional"))
      (node (ref "RP816") (pin "3") (pinfunction "3_3") (pintype "passive"))
    )
    (net (code "177") (name "/GPIOOUT7_6") (class "Default")
      (node (ref "GPIO7") (pin "7") (pinfunction "D6_7") (pintype "bidirectional"))
      (node (ref "RP816") (pin "5") (pinfunction "5_5") (pintype "passive"))
    )
    (net (code "178") (name "/GPIOOUT7_7") (class "Default")
      (node (ref "GPIO7") (pin "8") (pinfunction "D7_8") (pintype "bidirectional"))
      (node (ref "RP816") (pin "7") (pinfunction "7_7") (pintype "passive"))
    )
    (net (code "179") (name "/GPIOOUT7_8") (class "Default")
      (node (ref "GPIO7") (pin "9") (pinfunction "D8_9") (pintype "bidirectional"))
      (node (ref "R815") (pin "2") (pinfunction "2_2") (pintype "passive"))
    )
    (net (code "180") (name "/GPIOOUT7_G") (class "Default")
      (node (ref "GPIO7") (pin "10") (pinfunction "GND_10") (pintype "power_in"))
      (node (ref "R816") (pin "2") (pinfunction "2_2") (pintype "passive"))
    )
    (net (code "181") (name "/GPIOOUTC_0") (class "Default")
      (node (ref "GPIO") (pin "1") (pinfunction "1_1") (pintype "passive"))
      (node (ref "RP819") (pin "1") (pinfunction "1_1") (pintype "passive"))
    )
    (net (code "182") (name "/GPIOOUTC_1") (class "Default")
      (node (ref "GPIO") (pin "3") (pinfunction "3_3") (pintype "passive"))
      (node (ref "RP819") (pin "3") (pinfunction "3_3") (pintype "passive"))
    )
    (net (code "183") (name "/GPIOOUTC_2") (class "Default")
      (node (ref "GPIO") (pin "5") (pinfunction "5_5") (pintype "passive"))
      (node (ref "RP819") (pin "5") (pinfunction "5_5") (pintype "passive"))
    )
    (net (code "184") (name "/GPIOOUTC_3") (class "Default")
      (node (ref "GPIO") (pin "7") (pinfunction "7_7") (pintype "passive"))
      (node (ref "RP819") (pin "7") (pinfunction "7_7") (pintype "passive"))
    )
    (net (code "185") (name "/GPIOOUTC_4") (class "Default")
      (node (ref "GPIO") (pin "9") (pinfunction "9_9") (pintype "passive"))
      (node (ref "RP820") (pin "1") (pinfunction "1_1") (pintype "passive"))
    )
    (net (code "186") (name "/GPIOOUTC_5") (class "Default")
      (node (ref "GPIO") (pin "11") (pinfunction "11_11") (pintype "passive"))
      (node (ref "RP820") (pin "3") (pinfunction "3_3") (pintype "passive"))
    )
    (net (code "187") (name "/GPIOOUTC_6") (class "Default")
      (node (ref "GPIO") (pin "13") (pinfunction "13_13") (pintype "passive"))
      (node (ref "RP820") (pin "5") (pinfunction "5_5") (pintype "passive"))
    )
    (net (code "188") (name "/GPIOOUTC_7") (class "Default")
      (node (ref "GPIO") (pin "15") (pinfunction "15_15") (pintype "passive"))
      (node (ref "RP820") (pin "7") (pinfunction "7_7") (pintype "passive"))
    )
    (net (code "189") (name "/GPIOOUTC_8") (class "Default")
      (node (ref "GPIO") (pin "17") (pinfunction "17_17") (pintype "passive"))
      (node (ref "RP821") (pin "1") (pinfunction "1_1") (pintype "passive"))
    )
    (net (code "190") (name "/GPIOOUTC_9") (class "Default")
      (node (ref "GPIO") (pin "19") (pinfunction "19_19") (pintype "passive"))
      (node (ref "RP821") (pin "3") (pinfunction "3_3") (pintype "passive"))
    )
    (net (code "191") (name "/GPIOOUTC_10") (class "Default")
      (node (ref "GPIO") (pin "21") (pinfunction "21_21") (pintype "passive"))
      (node (ref "RP821") (pin "5") (pinfunction "5_5") (pintype "passive"))
    )
    (net (code "192") (name "/GPIOOUTC_11") (class "Default")
      (node (ref "GPIO") (pin "23") (pinfunction "23_23") (pintype "passive"))
      (node (ref "RP821") (pin "7") (pinfunction "7_7") (pintype "passive"))
    )
    (net (code "193") (name "/GPIOOUTC_12") (class "Default")
      (node (ref "GPIO") (pin "25") (pinfunction "25_25") (pintype "passive"))
      (node (ref "RP822") (pin "1") (pinfunction "1_1") (pintype "passive"))
    )
    (net (code "194") (name "/GPIOOUTC_13") (class "Default")
      (node (ref "GPIO") (pin "27") (pinfunction "27_27") (pintype "passive"))
      (node (ref "RP822") (pin "3") (pinfunction "3_3") (pintype "passive"))
    )
    (net (code "195") (name "/GPIOOUTC_14") (class "Default")
      (node (ref "GPIO") (pin "29") (pinfunction "29_29") (pintype "passive"))
      (node (ref "RP822") (pin "5") (pinfunction "5_5") (pintype "passive"))
    )
    (net (code "196") (name "/GPIOOUTC_15") (class "Default")
      (node (ref "GPIO") (pin "31") (pinfunction "31_31") (pintype "passive"))
      (node (ref "RP822") (pin "7") (pinfunction "7_7") (pintype "passive"))
    )
    (net (code "197") (name "/IIC1_SCL") (class "Default")
      (node (ref "R819") (pin "1") (pinfunction "1_1") (pintype "passive"))
      (node (ref "R821") (pin "1") (pinfunction "1_1") (pintype "passive"))
    )
    (net (code "198") (name "/IIC1_SDA") (class "Default")
      (node (ref "R820") (pin "1") (pinfunction "1_1") (pintype "passive"))
      (node (ref "R822") (pin "1") (pinfunction "1_1") (pintype "passive"))
    )
    (net (code "199") (name "/IIC2_SCL") (class "Default")
      (node (ref "RP823") (pin "5") (pinfunction "5_5") (pintype "passive"))
      (node (ref "ZLG7290") (pin "4") (pinfunction "SCL_4") (pintype "input"))
    )
    (net (code "200") (name "/IIC2_SDA") (class "Default")
      (node (ref "RP823") (pin "3") (pinfunction "3_3") (pintype "passive"))
      (node (ref "ZLG7290") (pin "6") (pinfunction "SDA_6") (pintype "bidirectional"))
    )
    (net (code "201") (name "/KEYPAD_INT") (class "Default")
      (node (ref "RP823") (pin "1") (pinfunction "1_1") (pintype "passive"))
      (node (ref "ZLG7290") (pin "8") (pinfunction "~{INT}_8") (pintype "output"))
    )
    (net (code "202") (name "/SPI2_MOSI") (class "Default")
      (node (ref "R818") (pin "1") (pinfunction "1_1") (pintype "passive"))
    )
    (net (code "203") (name "/TIM2_CH1") (class "Default")
      (node (ref "RP817") (pin "2") (pinfunction "2_2") (pintype "passive"))
    )
    (net (code "204") (name "/TIM2_CH2") (class "Default")
      (node (ref "RP817") (pin "4") (pinfunction "4_4") (pintype "passive"))
    )
    (net (code "205") (name "/TIM2_CH3") (class "Default")
      (node (ref "RP817") (pin "6") (pinfunction "6_6") (pintype "passive"))
    )
    (net (code "206") (name "/TIM2_CH4") (class "Default")
      (node (ref "RP817") (pin "8") (pinfunction "8_8") (pintype "passive"))
    )
    (net (code "207") (name "/TIM8_CH1") (class "Default")
      (node (ref "RP818") (pin "2") (pinfunction "2_2") (pintype "passive"))
    )
    (net (code "208") (name "/TIM8_CH2") (class "Default")
      (node (ref "RP818") (pin "4") (pinfunction "4_4") (pintype "passive"))
    )
    (net (code "209") (name "/TIM8_CH3") (class "Default")
      (node (ref "RP818") (pin "6") (pinfunction "6_6") (pintype "passive"))
    )
    (net (code "210") (name "/TIM8_CH4") (class "Default")
      (node (ref "RP818") (pin "8") (pinfunction "8_8") (pintype "passive"))
    )
    (net (code "211") (name "/TIM8_ETR") (class "Default")
      (node (ref "R817") (pin "2") (pinfunction "2_2") (pintype "passive"))
    )
    (net (code "212") (name "/USART1_RX") (class "Default")
      (node (ref "R824") (pin "2") (pinfunction "2_2") (pintype "passive"))
    )
    (net (code "213") (name "/USART1_TX") (class "Default")
      (node (ref "R823") (pin "2") (pinfunction "2_2") (pintype "passive"))
    )
    (net (code "214") (name "GND") (class "Default")
      (node (ref "AD9959") (pin "1") (pinfunction "GND_1") (pintype "power_in"))
      (node (ref "AD9959") (pin "10") (pinfunction "GND_10") (pintype "power_in"))
      (node (ref "AD9959") (pin "16") (pinfunction "GND_16") (pintype "power_in"))
      (node (ref "AD9959") (pin "6") (pinfunction "GND_6") (pintype "power_in"))
      (node (ref "C801") (pin "1") (pinfunction "1_1") (pintype "passive"))
      (node (ref "GPIO") (pin "10") (pinfunction "10_10") (pintype "passive"))
      (node (ref "GPIO") (pin "12") (pinfunction "12_12") (pintype "passive"))
      (node (ref "GPIO") (pin "14") (pinfunction "14_14") (pintype "passive"))
      (node (ref "GPIO") (pin "16") (pinfunction "16_16") (pintype "passive"))
      (node (ref "GPIO") (pin "18") (pinfunction "18_18") (pintype "passive"))
      (node (ref "GPIO") (pin "2") (pinfunction "2_2") (pintype "passive"))
      (node (ref "GPIO") (pin "20") (pinfunction "20_20") (pintype "passive"))
      (node (ref "GPIO") (pin "22") (pinfunction "22_22") (pintype "passive"))
      (node (ref "GPIO") (pin "24") (pinfunction "24_24") (pintype "passive"))
      (node (ref "GPIO") (pin "26") (pinfunction "26_26") (pintype "passive"))
      (node (ref "GPIO") (pin "28") (pinfunction "28_28") (pintype "passive"))
      (node (ref "GPIO") (pin "30") (pinfunction "30_30") (pintype "passive"))
      (node (ref "GPIO") (pin "32") (pinfunction "32_32") (pintype "passive"))
      (node (ref "GPIO") (pin "4") (pinfunction "4_4") (pintype "passive"))
      (node (ref "GPIO") (pin "6") (pinfunction "6_6") (pintype "passive"))
      (node (ref "GPIO") (pin "8") (pinfunction "8_8") (pintype "passive"))
      (node (ref "R802") (pin "1") (pinfunction "1_1") (pintype "passive"))
      (node (ref "R804") (pin "1") (pinfunction "1_1") (pintype "passive"))
      (node (ref "R806") (pin "1") (pinfunction "1_1") (pintype "passive"))
      (node (ref "R808") (pin "1") (pinfunction "1_1") (pintype "passive"))
      (node (ref "R810") (pin "1") (pinfunction "1_1") (pintype "passive"))
      (node (ref "R812") (pin "1") (pinfunction "1_1") (pintype "passive"))
      (node (ref "R814") (pin "1") (pinfunction "1_1") (pintype "passive"))
      (node (ref "R816") (pin "1") (pinfunction "1_1") (pintype "passive"))
      (node (ref "SERIAL") (pin "5") (pinfunction "5_5") (pintype "passive"))
      (node (ref "SERIAL") (pin "6") (pinfunction "6_6") (pintype "passive"))
      (node (ref "TIMER") (pin "9") (pinfunction "9_9") (pintype "passive"))
      (node (ref "ZLG7290") (pin "3") (pinfunction "GND_3") (pintype "power_in"))
      (node (ref "ZLG7290") (pin "5") (pinfunction "GND_5") (pintype "power_in"))
      (node (ref "ZLG7290") (pin "7") (pinfunction "GND_7") (pintype "power_in"))
      (node (ref "ZLG7290") (pin "9") (pinfunction "GND_9") (pintype "power_in"))
    )
    (net (code "215") (name "Net-(LED801-A)") (class "Default")
      (node (ref "LED801") (pin "1") (pinfunction "A_1") (pintype "passive"))
      (node (ref "RP823") (pin "7") (pinfunction "7_7") (pintype "passive"))
    )
    (net (code "216") (name "Net-(LED801-K)") (class "Default")
      (node (ref "LED801") (pin "2") (pinfunction "K_2") (pintype "passive"))
      (node (ref "ZLG7290") (pin "10") (pinfunction "LED_10") (pintype "output"))
    )
    (net (code "217") (name "Net-(R817-Pad1)") (class "Default")
      (node (ref "R817") (pin "1") (pinfunction "1_1") (pintype "passive"))
      (node (ref "TIMER") (pin "10") (pinfunction "10_10") (pintype "passive"))
    )
    (net (code "218") (name "Net-(R821-Pad2)") (class "Default")
      (node (ref "R821") (pin "2") (pinfunction "2_2") (pintype "passive"))
      (node (ref "SERIAL") (pin "1") (pinfunction "1_1") (pintype "passive"))
    )
    (net (code "219") (name "Net-(R822-Pad2)") (class "Default")
      (node (ref "R822") (pin "2") (pinfunction "2_2") (pintype "passive"))
      (node (ref "SERIAL") (pin "3") (pinfunction "3_3") (pintype "passive"))
    )
    (net (code "220") (name "Net-(R823-Pad1)") (class "Default")
      (node (ref "R823") (pin "1") (pinfunction "1_1") (pintype "passive"))
      (node (ref "SERIAL") (pin "2") (pinfunction "2_2") (pintype "passive"))
    )
    (net (code "221") (name "Net-(R824-Pad1)") (class "Default")
      (node (ref "R824") (pin "1") (pinfunction "1_1") (pintype "passive"))
      (node (ref "SERIAL") (pin "4") (pinfunction "4_4") (pintype "passive"))
    )
    (net (code "222") (name "Net-(RP817-Pad1)") (class "Default")
      (node (ref "RP817") (pin "1") (pinfunction "1_1") (pintype "passive"))
      (node (ref "TIMER") (pin "1") (pinfunction "1_1") (pintype "passive"))
    )
    (net (code "223") (name "Net-(RP817-Pad3)") (class "Default")
      (node (ref "RP817") (pin "3") (pinfunction "3_3") (pintype "passive"))
      (node (ref "TIMER") (pin "3") (pinfunction "3_3") (pintype "passive"))
    )
    (net (code "224") (name "Net-(RP817-Pad5)") (class "Default")
      (node (ref "RP817") (pin "5") (pinfunction "5_5") (pintype "passive"))
      (node (ref "TIMER") (pin "5") (pinfunction "5_5") (pintype "passive"))
    )
    (net (code "225") (name "Net-(RP817-Pad7)") (class "Default")
      (node (ref "RP817") (pin "7") (pinfunction "7_7") (pintype "passive"))
      (node (ref "TIMER") (pin "7") (pinfunction "7_7") (pintype "passive"))
    )
    (net (code "226") (name "Net-(RP818-Pad1)") (class "Default")
      (node (ref "RP818") (pin "1") (pinfunction "1_1") (pintype "passive"))
      (node (ref "TIMER") (pin "2") (pinfunction "2_2") (pintype "passive"))
    )
    (net (code "227") (name "Net-(RP818-Pad3)") (class "Default")
      (node (ref "RP818") (pin "3") (pinfunction "3_3") (pintype "passive"))
      (node (ref "TIMER") (pin "4") (pinfunction "4_4") (pintype "passive"))
    )
    (net (code "228") (name "Net-(RP818-Pad5)") (class "Default")
      (node (ref "RP818") (pin "5") (pinfunction "5_5") (pintype "passive"))
      (node (ref "TIMER") (pin "6") (pinfunction "6_6") (pintype "passive"))
    )
    (net (code "229") (name "Net-(RP818-Pad7)") (class "Default")
      (node (ref "RP818") (pin "7") (pinfunction "7_7") (pintype "passive"))
      (node (ref "TIMER") (pin "8") (pinfunction "8_8") (pintype "passive"))
    )
    (net (code "230") (name "V33") (class "Default")
      (node (ref "C801") (pin "2") (pinfunction "2_2") (pintype "passive"))
      (node (ref "R819") (pin "2") (pinfunction "2_2") (pintype "passive"))
      (node (ref "R820") (pin "2") (pinfunction "2_2") (pintype "passive"))
      (node (ref "RP823") (pin "2") (pinfunction "2_2") (pintype "passive"))
      (node (ref "RP823") (pin "4") (pinfunction "4_4") (pintype "passive"))
      (node (ref "RP823") (pin "6") (pinfunction "6_6") (pintype "passive"))
      (node (ref "RP823") (pin "8") (pinfunction "8_8") (pintype "passive"))
      (node (ref "ZLG7290") (pin "1") (pinfunction "VCC_1") (pintype "power_in"))
      (node (ref "ZLG7290") (pin "2") (pinfunction "VCC_2") (pintype "power_in"))
    )
  )
)
